# Motor.net
KiCad netlist of a schematic drawn in Altium Designer
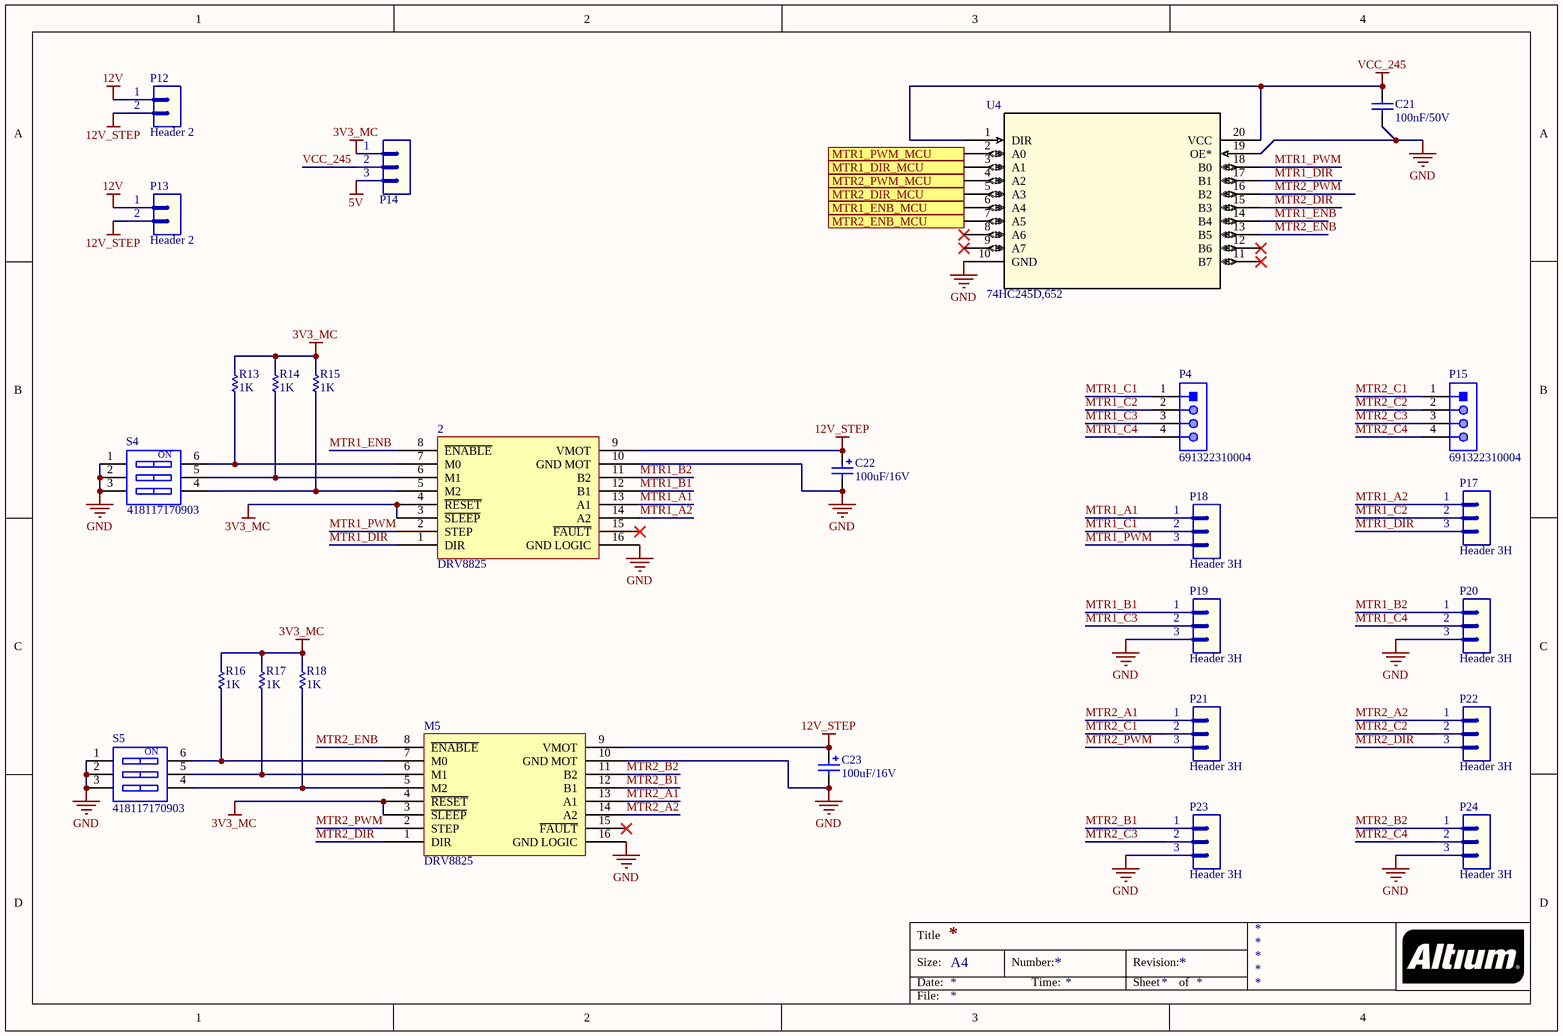
[diagram p0: Motor.schdoc]

(export (version "E")
  (design (tool "Eeschema 10.0.6"))
  (components
    (comp (ref "2")
      (value "DRV8825")
      (footprint "DRV8825 (1):PCBComponent_1")
      (libsource (lib "Bai1") (part "DRV8825"))
    )
    (comp (ref "C21")
      (value "100nF/50V")
      (footprint "CAP-SM-0805")
      (description "CAP CER 0.1UF 50V Y5V 0805")
      (fields
        (field (name "MANUFACTURER") "Samsung Electro-Mechanics")
        (field (name "MANUFACTURER PART NUMBER") "CL21F104ZBCNNNC")
      )
      (libsource (lib "Capacitor") (part "Cap-100nF-50V-0805"))
    )
    (comp (ref "C22")
      (value "100uF/16V")
      (footprint "CAP-SM-AL-SIZE-D-D6L6")
      (description "CAP ALUM 100UF 20% 16V SMD")
      (fields
        (field (name "MANUFACTURER") "Nichicon")
        (field (name "MANUFACTURER PART NUMBER") "UWX1C101MCL1GB")
      )
      (libsource (lib "Capacitor") (part "Cap-Al-100uF-16V-D6L5"))
    )
    (comp (ref "C23")
      (value "100uF/16V")
      (footprint "CAP-SM-AL-SIZE-D-D6L6")
      (description "CAP ALUM 100UF 20% 16V SMD")
      (fields
        (field (name "MANUFACTURER") "Nichicon")
        (field (name "MANUFACTURER PART NUMBER") "UWX1C101MCL1GB")
      )
      (libsource (lib "Capacitor") (part "Cap-Al-100uF-16V-D6L5"))
    )
    (comp (ref "M5")
      (value "DRV8825")
      (footprint "DRV8825 (1):PCBComponent_1")
      (libsource (lib "Bai1") (part "DRV8825"))
    )
    (comp (ref "P4")
      (value "691322310004")
      (footprint "691322310004")
      (description "WR-TBL Serie 322 Horizontal PCB Header, Pluggable, pitch 3.81mm, 4p")
      (fields (field (name "PUBLISHER") "Wurth Elektronik"))
      (libsource (lib "o162719v243 Altium_WR-TBL (rev19a)") (part "691322310004"))
    )
    (comp (ref "P12")
      (value "Header 2")
      (footprint "JP2")
      (description "Header, 2-Pin")
      (fields (field (name "PUBLISHER") "Altium Limited"))
      (libsource (lib "Header-connector") (part "Header 2"))
    )
    (comp (ref "P13")
      (value "Header 2")
      (footprint "JP2")
      (description "Header, 2-Pin")
      (fields (field (name "PUBLISHER") "Altium Limited"))
      (libsource (lib "Header-connector") (part "Header 2"))
    )
    (comp (ref "P14")
      (value "Header 3")
      (footprint "JP3")
      (description "Header, 3-Pin")
      (fields (field (name "PUBLISHER") "Altium Limited"))
      (libsource (lib "Header-connector") (part "Header 3"))
    )
    (comp (ref "P15")
      (value "691322310004")
      (footprint "691322310004")
      (description "WR-TBL Serie 322 Horizontal PCB Header, Pluggable, pitch 3.81mm, 4p")
      (fields (field (name "PUBLISHER") "Wurth Elektronik"))
      (libsource (lib "o162719v243 Altium_WR-TBL (rev19a)") (part "691322310004"))
    )
    (comp (ref "P17")
      (value "Header 3H")
      (footprint "JP3H")
      (description "Header, 3-Pin, Right Angle")
      (fields (field (name "PUBLISHER") "Altium Limited"))
      (libsource (lib "Header-connector") (part "Header 3H"))
    )
    (comp (ref "P18")
      (value "Header 3H")
      (footprint "JP3H")
      (description "Header, 3-Pin, Right Angle")
      (fields (field (name "PUBLISHER") "Altium Limited"))
      (libsource (lib "Header-connector") (part "Header 3H"))
    )
    (comp (ref "P19")
      (value "Header 3H")
      (footprint "JP3H")
      (description "Header, 3-Pin, Right Angle")
      (fields (field (name "PUBLISHER") "Altium Limited"))
      (libsource (lib "Header-connector") (part "Header 3H"))
    )
    (comp (ref "P20")
      (value "Header 3H")
      (footprint "JP3H")
      (description "Header, 3-Pin, Right Angle")
      (fields (field (name "PUBLISHER") "Altium Limited"))
      (libsource (lib "Header-connector") (part "Header 3H"))
    )
    (comp (ref "P21")
      (value "Header 3H")
      (footprint "JP3H")
      (description "Header, 3-Pin, Right Angle")
      (fields (field (name "PUBLISHER") "Altium Limited"))
      (libsource (lib "Header-connector") (part "Header 3H"))
    )
    (comp (ref "P22")
      (value "Header 3H")
      (footprint "JP3H")
      (description "Header, 3-Pin, Right Angle")
      (fields (field (name "PUBLISHER") "Altium Limited"))
      (libsource (lib "Header-connector") (part "Header 3H"))
    )
    (comp (ref "P23")
      (value "Header 3H")
      (footprint "JP3H")
      (description "Header, 3-Pin, Right Angle")
      (fields (field (name "PUBLISHER") "Altium Limited"))
      (libsource (lib "Header-connector") (part "Header 3H"))
    )
    (comp (ref "P24")
      (value "Header 3H")
      (footprint "JP3H")
      (description "Header, 3-Pin, Right Angle")
      (fields (field (name "PUBLISHER") "Altium Limited"))
      (libsource (lib "Header-connector") (part "Header 3H"))
    )
    (comp (ref "R13")
      (value "1K")
      (footprint "RES-SM-0805")
      (fields (field (name "Comment") "Resistor 1/4W"))
      (libsource (lib "PIF_C16_lib (1)") (part "RES"))
    )
    (comp (ref "R14")
      (value "1K")
      (footprint "RES-SM-0805")
      (fields (field (name "Comment") "Resistor 1/4W"))
      (libsource (lib "PIF_C16_lib (1)") (part "RES"))
    )
    (comp (ref "R15")
      (value "1K")
      (footprint "RES-SM-0805")
      (fields (field (name "Comment") "Resistor 1/4W"))
      (libsource (lib "PIF_C16_lib (1)") (part "RES"))
    )
    (comp (ref "R16")
      (value "1K")
      (footprint "RES-SM-0805")
      (fields (field (name "Comment") "Resistor 1/4W"))
      (libsource (lib "PIF_C16_lib (1)") (part "RES"))
    )
    (comp (ref "R17")
      (value "1K")
      (footprint "RES-SM-0805")
      (fields (field (name "Comment") "Resistor 1/4W"))
      (libsource (lib "PIF_C16_lib (1)") (part "RES"))
    )
    (comp (ref "R18")
      (value "1K")
      (footprint "RES-SM-0805")
      (fields (field (name "Comment") "Resistor 1/4W"))
      (libsource (lib "PIF_C16_lib (1)") (part "RES"))
    )
    (comp (ref "S4")
      (value "418117170903")
      (footprint "SWITCH3:PCBComponent_1")
      (description "WS-DITV Compact THT Dip Switch, Flat Actuator, pitch 2.54mm, 3p")
      (fields (field (name "PUBLISHER") "Wurth Elektronik"))
      (libsource (lib "418117170903_Altium_WS-DITV_rev19a") (part "418117170903"))
    )
    (comp (ref "S5")
      (value "418117170903")
      (footprint "SWITCH3:PCBComponent_1")
      (description "WS-DITV Compact THT Dip Switch, Flat Actuator, pitch 2.54mm, 3p")
      (fields (field (name "PUBLISHER") "Wurth Elektronik"))
      (libsource (lib "418117170903_Altium_WS-DITV_rev19a") (part "418117170903"))
    )
    (comp (ref "U4")
      (value "74HC245D,652")
      (footprint "SOT163-1_NEX")
      (description "No Description Available")
      (fields (field (name "COPYRIGHT") "Copyright (C) 2016 Accelerated Designs. All rights reserved"))
      (libsource (lib "2020-06-20_03-26-16") (part "74HC245D,652"))
    )
  )
  (nets
    (net (code "1") (name "/MTR1_A1") (class "Default")
      (node (ref "2") (pin "13") (pinfunction "A1_13") (pintype "passive"))
      (node (ref "P18") (pin "1") (pinfunction "1_1") (pintype "passive"))
    )
    (net (code "2") (name "/MTR1_A2") (class "Default")
      (node (ref "2") (pin "14") (pinfunction "A2_14") (pintype "passive"))
      (node (ref "P17") (pin "1") (pinfunction "1_1") (pintype "passive"))
    )
    (net (code "3") (name "/MTR1_B1") (class "Default")
      (node (ref "2") (pin "12") (pinfunction "B1_12") (pintype "passive"))
      (node (ref "P19") (pin "1") (pinfunction "1_1") (pintype "passive"))
    )
    (net (code "4") (name "/MTR1_B2") (class "Default")
      (node (ref "2") (pin "11") (pinfunction "B2_11") (pintype "passive"))
      (node (ref "P20") (pin "1") (pinfunction "1_1") (pintype "passive"))
    )
    (net (code "5") (name "/MTR1_C1") (class "Default")
      (node (ref "P18") (pin "2") (pinfunction "2_2") (pintype "passive"))
      (node (ref "P4") (pin "1") (pinfunction "1_1") (pintype "passive"))
    )
    (net (code "6") (name "/MTR1_C2") (class "Default")
      (node (ref "P17") (pin "2") (pinfunction "2_2") (pintype "passive"))
      (node (ref "P4") (pin "2") (pinfunction "2_2") (pintype "passive"))
    )
    (net (code "7") (name "/MTR1_C3") (class "Default")
      (node (ref "P19") (pin "2") (pinfunction "2_2") (pintype "passive"))
      (node (ref "P4") (pin "3") (pinfunction "3_3") (pintype "passive"))
    )
    (net (code "8") (name "/MTR1_C4") (class "Default")
      (node (ref "P20") (pin "2") (pinfunction "2_2") (pintype "passive"))
      (node (ref "P4") (pin "4") (pinfunction "4_4") (pintype "passive"))
    )
    (net (code "9") (name "/MTR1_DIR") (class "Default")
      (node (ref "2") (pin "1") (pinfunction "DIR_1") (pintype "passive"))
      (node (ref "P17") (pin "3") (pinfunction "3_3") (pintype "passive"))
      (node (ref "U4") (pin "17") (pinfunction "B1_17") (pintype "bidirectional"))
    )
    (net (code "10") (name "/MTR1_DIR_MCU") (class "Default")
      (node (ref "U4") (pin "3") (pinfunction "A1_3") (pintype "bidirectional"))
    )
    (net (code "11") (name "/MTR1_ENB") (class "Default")
      (node (ref "2") (pin "8") (pinfunction "~{ENABLE}_8") (pintype "passive"))
      (node (ref "U4") (pin "14") (pinfunction "B4_14") (pintype "bidirectional"))
    )
    (net (code "12") (name "/MTR1_ENB_MCU") (class "Default")
      (node (ref "U4") (pin "6") (pinfunction "A4_6") (pintype "bidirectional"))
    )
    (net (code "13") (name "/MTR1_PWM") (class "Default")
      (node (ref "2") (pin "2") (pinfunction "STEP_2") (pintype "passive"))
      (node (ref "P18") (pin "3") (pinfunction "3_3") (pintype "passive"))
      (node (ref "U4") (pin "18") (pinfunction "B0_18") (pintype "bidirectional"))
    )
    (net (code "14") (name "/MTR1_PWM_MCU") (class "Default")
      (node (ref "U4") (pin "2") (pinfunction "A0_2") (pintype "bidirectional"))
    )
    (net (code "15") (name "/MTR2_A1") (class "Default")
      (node (ref "M5") (pin "13") (pinfunction "A1_13") (pintype "passive"))
      (node (ref "P21") (pin "1") (pinfunction "1_1") (pintype "passive"))
    )
    (net (code "16") (name "/MTR2_A2") (class "Default")
      (node (ref "M5") (pin "14") (pinfunction "A2_14") (pintype "passive"))
      (node (ref "P22") (pin "1") (pinfunction "1_1") (pintype "passive"))
    )
    (net (code "17") (name "/MTR2_B1") (class "Default")
      (node (ref "M5") (pin "12") (pinfunction "B1_12") (pintype "passive"))
      (node (ref "P23") (pin "1") (pinfunction "1_1") (pintype "passive"))
    )
    (net (code "18") (name "/MTR2_B2") (class "Default")
      (node (ref "M5") (pin "11") (pinfunction "B2_11") (pintype "passive"))
      (node (ref "P24") (pin "1") (pinfunction "1_1") (pintype "passive"))
    )
    (net (code "19") (name "/MTR2_C1") (class "Default")
      (node (ref "P15") (pin "1") (pinfunction "1_1") (pintype "passive"))
      (node (ref "P21") (pin "2") (pinfunction "2_2") (pintype "passive"))
    )
    (net (code "20") (name "/MTR2_C2") (class "Default")
      (node (ref "P15") (pin "2") (pinfunction "2_2") (pintype "passive"))
      (node (ref "P22") (pin "2") (pinfunction "2_2") (pintype "passive"))
    )
    (net (code "21") (name "/MTR2_C3") (class "Default")
      (node (ref "P15") (pin "3") (pinfunction "3_3") (pintype "passive"))
      (node (ref "P23") (pin "2") (pinfunction "2_2") (pintype "passive"))
    )
    (net (code "22") (name "/MTR2_C4") (class "Default")
      (node (ref "P15") (pin "4") (pinfunction "4_4") (pintype "passive"))
      (node (ref "P24") (pin "2") (pinfunction "2_2") (pintype "passive"))
    )
    (net (code "23") (name "/MTR2_DIR") (class "Default")
      (node (ref "M5") (pin "1") (pinfunction "DIR_1") (pintype "passive"))
      (node (ref "P22") (pin "3") (pinfunction "3_3") (pintype "passive"))
      (node (ref "U4") (pin "15") (pinfunction "B3_15") (pintype "bidirectional"))
    )
    (net (code "24") (name "/MTR2_DIR_MCU") (class "Default")
      (node (ref "U4") (pin "5") (pinfunction "A3_5") (pintype "bidirectional"))
    )
    (net (code "25") (name "/MTR2_ENB") (class "Default")
      (node (ref "M5") (pin "8") (pinfunction "~{ENABLE}_8") (pintype "passive"))
      (node (ref "U4") (pin "13") (pinfunction "B5_13") (pintype "bidirectional"))
    )
    (net (code "26") (name "/MTR2_ENB_MCU") (class "Default")
      (node (ref "U4") (pin "7") (pinfunction "A5_7") (pintype "bidirectional"))
    )
    (net (code "27") (name "/MTR2_PWM") (class "Default")
      (node (ref "M5") (pin "2") (pinfunction "STEP_2") (pintype "passive"))
      (node (ref "P21") (pin "3") (pinfunction "3_3") (pintype "passive"))
      (node (ref "U4") (pin "16") (pinfunction "B2_16") (pintype "bidirectional"))
    )
    (net (code "28") (name "/MTR2_PWM_MCU") (class "Default")
      (node (ref "U4") (pin "4") (pinfunction "A2_4") (pintype "bidirectional"))
    )
    (net (code "29") (name "3V3_MC") (class "Default")
      (node (ref "2") (pin "3") (pinfunction "~{SLEEP}_3") (pintype "passive"))
      (node (ref "2") (pin "4") (pinfunction "~{RESET}_4") (pintype "passive"))
      (node (ref "M5") (pin "3") (pinfunction "~{SLEEP}_3") (pintype "passive"))
      (node (ref "M5") (pin "4") (pinfunction "~{RESET}_4") (pintype "passive"))
      (node (ref "P14") (pin "1") (pinfunction "1_1") (pintype "passive"))
      (node (ref "R13") (pin "2") (pintype "passive"))
      (node (ref "R14") (pin "2") (pintype "passive"))
      (node (ref "R15") (pin "2") (pintype "passive"))
      (node (ref "R16") (pin "2") (pintype "passive"))
      (node (ref "R17") (pin "2") (pintype "passive"))
      (node (ref "R18") (pin "2") (pintype "passive"))
    )
    (net (code "30") (name "5V") (class "Default")
      (node (ref "P14") (pin "3") (pinfunction "3_3") (pintype "passive"))
    )
    (net (code "31") (name "12V") (class "Default")
      (node (ref "P12") (pin "1") (pinfunction "1_1") (pintype "passive"))
      (node (ref "P13") (pin "1") (pinfunction "1_1") (pintype "passive"))
    )
    (net (code "32") (name "12V_STEP") (class "Default")
      (node (ref "2") (pin "9") (pinfunction "VMOT_9") (pintype "passive"))
      (node (ref "C22") (pin "1") (pinfunction "1_1") (pintype "passive"))
      (node (ref "C23") (pin "1") (pinfunction "1_1") (pintype "passive"))
      (node (ref "M5") (pin "9") (pinfunction "VMOT_9") (pintype "passive"))
      (node (ref "P12") (pin "2") (pinfunction "2_2") (pintype "passive"))
      (node (ref "P13") (pin "2") (pinfunction "2_2") (pintype "passive"))
    )
    (net (code "33") (name "GND") (class "Default")
      (node (ref "2") (pin "10") (pinfunction "GND_MOT_10") (pintype "passive"))
      (node (ref "2") (pin "16") (pinfunction "GND_LOGIC_16") (pintype "passive"))
      (node (ref "C21") (pin "1") (pinfunction "1_1") (pintype "passive"))
      (node (ref "C22") (pin "2") (pinfunction "2_2") (pintype "passive"))
      (node (ref "C23") (pin "2") (pinfunction "2_2") (pintype "passive"))
      (node (ref "M5") (pin "10") (pinfunction "GND_MOT_10") (pintype "passive"))
      (node (ref "M5") (pin "16") (pinfunction "GND_LOGIC_16") (pintype "passive"))
      (node (ref "P19") (pin "3") (pinfunction "3_3") (pintype "passive"))
      (node (ref "P20") (pin "3") (pinfunction "3_3") (pintype "passive"))
      (node (ref "P23") (pin "3") (pinfunction "3_3") (pintype "passive"))
      (node (ref "P24") (pin "3") (pinfunction "3_3") (pintype "passive"))
      (node (ref "S4") (pin "1") (pinfunction "1_1") (pintype "passive"))
      (node (ref "S4") (pin "2") (pinfunction "2_2") (pintype "passive"))
      (node (ref "S4") (pin "3") (pinfunction "3_3") (pintype "passive"))
      (node (ref "S5") (pin "1") (pinfunction "1_1") (pintype "passive"))
      (node (ref "S5") (pin "2") (pinfunction "2_2") (pintype "passive"))
      (node (ref "S5") (pin "3") (pinfunction "3_3") (pintype "passive"))
      (node (ref "U4") (pin "10") (pinfunction "GND_10") (pintype "power_in"))
      (node (ref "U4") (pin "19") (pinfunction "OE*_19") (pintype "input"))
    )
    (net (code "34") (name "Net-(2-M0)") (class "Default")
      (node (ref "2") (pin "7") (pinfunction "M0_7") (pintype "passive"))
      (node (ref "R13") (pin "1") (pintype "passive"))
      (node (ref "S4") (pin "6") (pinfunction "6_6") (pintype "passive"))
    )
    (net (code "35") (name "Net-(2-M1)") (class "Default")
      (node (ref "2") (pin "6") (pinfunction "M1_6") (pintype "passive"))
      (node (ref "R14") (pin "1") (pintype "passive"))
      (node (ref "S4") (pin "5") (pinfunction "5_5") (pintype "passive"))
    )
    (net (code "36") (name "Net-(2-M2)") (class "Default")
      (node (ref "2") (pin "5") (pinfunction "M2_5") (pintype "passive"))
      (node (ref "R15") (pin "1") (pintype "passive"))
      (node (ref "S4") (pin "4") (pinfunction "4_4") (pintype "passive"))
    )
    (net (code "37") (name "Net-(M5-M0)") (class "Default")
      (node (ref "M5") (pin "7") (pinfunction "M0_7") (pintype "passive"))
      (node (ref "R16") (pin "1") (pintype "passive"))
      (node (ref "S5") (pin "6") (pinfunction "6_6") (pintype "passive"))
    )
    (net (code "38") (name "Net-(M5-M1)") (class "Default")
      (node (ref "M5") (pin "6") (pinfunction "M1_6") (pintype "passive"))
      (node (ref "R17") (pin "1") (pintype "passive"))
      (node (ref "S5") (pin "5") (pinfunction "5_5") (pintype "passive"))
    )
    (net (code "39") (name "Net-(M5-M2)") (class "Default")
      (node (ref "M5") (pin "5") (pinfunction "M2_5") (pintype "passive"))
      (node (ref "R18") (pin "1") (pintype "passive"))
      (node (ref "S5") (pin "4") (pinfunction "4_4") (pintype "passive"))
    )
    (net (code "40") (name "VCC_245") (class "Default")
      (node (ref "C21") (pin "2") (pinfunction "2_2") (pintype "passive"))
      (node (ref "P14") (pin "2") (pinfunction "2_2") (pintype "passive"))
      (node (ref "U4") (pin "1") (pinfunction "DIR_1") (pintype "input"))
      (node (ref "U4") (pin "20") (pinfunction "VCC_20") (pintype "power_in"))
    )
    (net (code "41") (name "unconnected-(2-~{FAULT}-Pad15)") (class "Default")
      (node (ref "2") (pin "15") (pinfunction "~{FAULT}_15") (pintype "passive+no_connect"))
    )
    (net (code "42") (name "unconnected-(M5-~{FAULT}-Pad15)") (class "Default")
      (node (ref "M5") (pin "15") (pinfunction "~{FAULT}_15") (pintype "passive+no_connect"))
    )
    (net (code "43") (name "unconnected-(U4-A6-Pad8)") (class "Default")
      (node (ref "U4") (pin "8") (pinfunction "A6_8") (pintype "bidirectional+no_connect"))
    )
    (net (code "44") (name "unconnected-(U4-A7-Pad9)") (class "Default")
      (node (ref "U4") (pin "9") (pinfunction "A7_9") (pintype "bidirectional+no_connect"))
    )
    (net (code "45") (name "unconnected-(U4-B6-Pad12)") (class "Default")
      (node (ref "U4") (pin "12") (pinfunction "B6_12") (pintype "bidirectional+no_connect"))
    )
    (net (code "46") (name "unconnected-(U4-B7-Pad11)") (class "Default")
      (node (ref "U4") (pin "11") (pinfunction "B7_11") (pintype "bidirectional+no_connect"))
    )
  )
)
